# PowerManager.net
KiCad netlist of a schematic drawn in Altium Designer
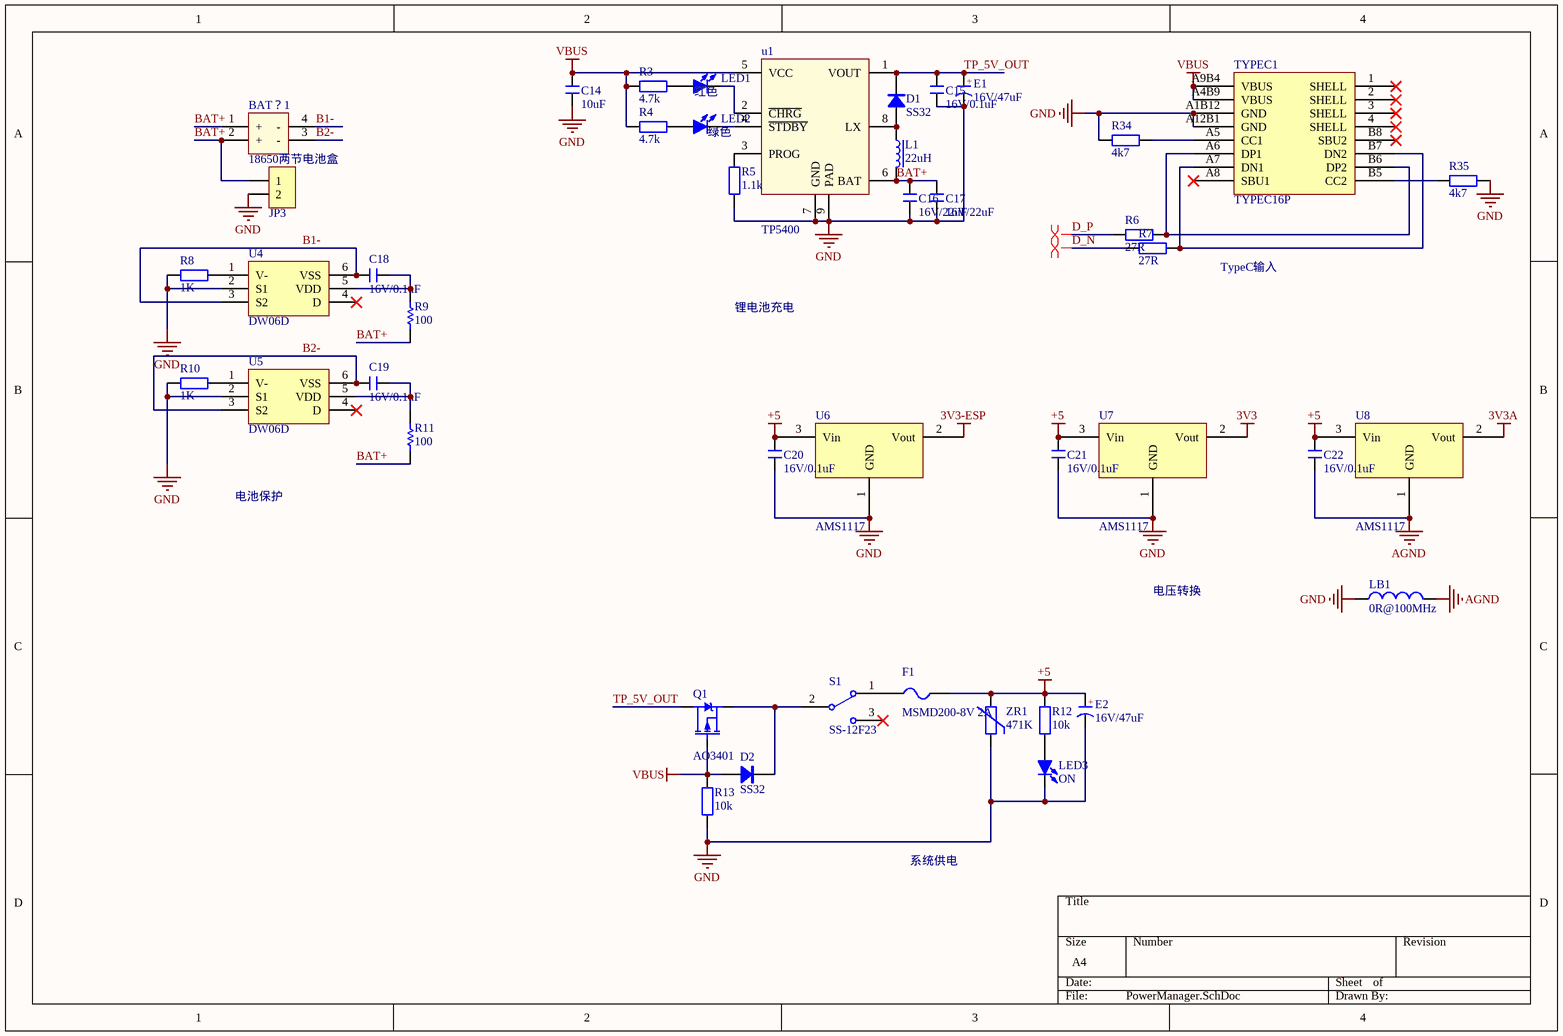
[diagram p0: PowerManager.SchDoc]

(export (version "E")
  (design (tool "Eeschema 10.0.6"))
  (components
    (comp (ref "BAT？1")
      (value "18650两节电池盒")
      (footprint "18650两节电池盒")
      (libsource (lib "Schlib1") (part "18650两节电池盒"))
    )
    (comp (ref "C14")
      (value "10uF")
      (footprint "C 0603_L")
      (description "无极性贴片电容")
      (fields (field (name "版权归属") "源创客"))
      (libsource (lib "3.1   - 电阻-电容-电感") (part "C"))
    )
    (comp (ref "C15")
      (value "16V/0.1uF")
      (footprint "C 1206_L")
      (description "无极性贴片电容")
      (fields (field (name "版权归属") "源创客"))
      (libsource (lib "3.1   - 电阻-电容-电感") (part "C"))
    )
    (comp (ref "C16")
      (value "16V/22uF")
      (footprint "C 1206_L")
      (description "无极性贴片电容")
      (fields (field (name "版权归属") "源创客"))
      (libsource (lib "3.1   - 电阻-电容-电感") (part "C"))
    )
    (comp (ref "C17")
      (value "16V/22uF")
      (footprint "C 1206_L")
      (description "无极性贴片电容")
      (fields (field (name "版权归属") "源创客"))
      (libsource (lib "3.1   - 电阻-电容-电感") (part "C"))
    )
    (comp (ref "C18")
      (value "16V/0.1uF")
      (footprint "C 1206_L")
      (description "无极性贴片电容")
      (fields (field (name "版权归属") "源创客"))
      (libsource (lib "3.1   - 电阻-电容-电感") (part "C"))
    )
    (comp (ref "C19")
      (value "16V/0.1uF")
      (footprint "C 1206_L")
      (description "无极性贴片电容")
      (fields (field (name "版权归属") "源创客"))
      (libsource (lib "3.1   - 电阻-电容-电感") (part "C"))
    )
    (comp (ref "C20")
      (value "16V/0.1uF")
      (footprint "C 1206_L")
      (description "无极性贴片电容")
      (fields (field (name "版权归属") "源创客"))
      (libsource (lib "3.1   - 电阻-电容-电感") (part "C"))
    )
    (comp (ref "C21")
      (value "16V/0.1uF")
      (footprint "C 1206_L")
      (description "无极性贴片电容")
      (fields (field (name "版权归属") "源创客"))
      (libsource (lib "3.1   - 电阻-电容-电感") (part "C"))
    )
    (comp (ref "C22")
      (value "16V/0.1uF")
      (footprint "C 1206_L")
      (description "无极性贴片电容")
      (fields (field (name "版权归属") "源创客"))
      (libsource (lib "3.1   - 电阻-电容-电感") (part "C"))
    )
    (comp (ref "D1")
      (value "SS32")
      (footprint "SMA")
      (description "肖特基二极管")
      (fields (field (name "版权归属") "源创客"))
      (libsource (lib "8.1   - 二极管-整流桥") (part "SS210"))
    )
    (comp (ref "D2")
      (value "SS32")
      (footprint "SMA")
      (description "肖特基二极管")
      (fields (field (name "版权归属") "源创客"))
      (libsource (lib "8.1   - 二极管-整流桥") (part "SS210"))
    )
    (comp (ref "E1")
      (value "16V/47uF")
      (footprint "CM C(5*5.4)")
      (description "贴片电解电容")
      (fields (field (name "版权归属") "源创客"))
      (libsource (lib "3.1   - 电阻-电容-电感") (part "C-CM"))
    )
    (comp (ref "E2")
      (value "16V/47uF")
      (footprint "CM C(5*5.4)")
      (description "贴片电解电容")
      (fields (field (name "版权归属") "源创客"))
      (libsource (lib "3.1   - 电阻-电容-电感") (part "C-CM"))
    )
    (comp (ref "F1")
      (value "MSMD200-8V 2A")
      (footprint "FU 1206")
      (description "贴片保险丝")
      (fields (field (name "版权归属") "源创客"))
      (libsource (lib "10.1 - 保险丝-晶振") (part "FU"))
    )
    (comp (ref "JP3")
      (value "HDR-1X2")
      (footprint "XH2.54-WS-2P")
      (description "2P接插件")
      (fields (field (name "版权归属") "源创客"))
      (libsource (lib "4.6   - 接插件-脚距2.54") (part "Header 2"))
    )
    (comp (ref "L1")
      (value "22uH")
      (footprint "NR4020")
      (description "NR磁胶电感")
      (fields (field (name "版权归属") "源创客"))
      (libsource (lib "3.1   - 电阻-电容-电感") (part "L-NR"))
    )
    (comp (ref "LB1")
      (value "0R@100MHz")
      (footprint "FB 1206_L")
      (description "磁珠")
      (fields (field (name "版权归属") "源创客"))
      (libsource (lib "3.1   - 电阻-电容-电感") (part "LB"))
    )
    (comp (ref "LED1")
      (value "红色")
      (footprint "LED 0603R")
      (description "贴片LED")
      (fields (field (name "版权归属") "源创客"))
      (libsource (lib "9.1   - LED") (part "LED-SMD"))
    )
    (comp (ref "LED2")
      (value "绿色")
      (footprint "LED 0603G")
      (description "贴片LED")
      (fields (field (name "版权归属") "源创客"))
      (libsource (lib "9.1   - LED") (part "LED-SMD"))
    )
    (comp (ref "LED3")
      (value "ON")
      (footprint "LED 0603R")
      (description "贴片LED")
      (fields (field (name "版权归属") "源创客"))
      (libsource (lib "9.1   - LED") (part "LED-SMD"))
    )
    (comp (ref "Q1")
      (value "AO3401")
      (footprint "SOT23")
      (description "P沟道场效应管")
      (libsource (lib "MOS管") (part "P-MOS"))
    )
    (comp (ref "R3")
      (value "4.7k")
      (footprint "R 0603_L")
      (description "贴片电阻")
      (fields (field (name "版权归属") "源创客"))
      (libsource (lib "3.1   - 电阻-电容-电感") (part "R"))
    )
    (comp (ref "R4")
      (value "4.7k")
      (footprint "R 0603_L")
      (description "贴片电阻")
      (fields (field (name "版权归属") "源创客"))
      (libsource (lib "3.1   - 电阻-电容-电感") (part "R"))
    )
    (comp (ref "R5")
      (value "1.1k")
      (footprint "R 0603_L")
      (description "贴片电阻")
      (fields (field (name "版权归属") "源创客"))
      (libsource (lib "3.1   - 电阻-电容-电感") (part "R"))
    )
    (comp (ref "R6")
      (value "27R")
      (footprint "R 0603_L")
      (description "贴片电阻")
      (fields (field (name "版权归属") "源创客"))
      (libsource (lib "3.1   - 电阻-电容-电感") (part "R"))
    )
    (comp (ref "R7")
      (value "27R")
      (footprint "R 0603_L")
      (description "贴片电阻")
      (fields (field (name "版权归属") "源创客"))
      (libsource (lib "3.1   - 电阻-电容-电感") (part "R"))
    )
    (comp (ref "R8")
      (value "1K")
      (footprint "R 0603_L")
      (description "贴片电阻")
      (fields (field (name "版权归属") "源创客"))
      (libsource (lib "3.1   - 电阻-电容-电感") (part "R"))
    )
    (comp (ref "R9") (value "100") (footprint "0603R") (libsource (lib "电阻") (part "RES")))
    (comp (ref "R10")
      (value "1K")
      (footprint "R 0603_L")
      (description "贴片电阻")
      (fields (field (name "版权归属") "源创客"))
      (libsource (lib "3.1   - 电阻-电容-电感") (part "R"))
    )
    (comp (ref "R11") (value "100") (footprint "0603R") (libsource (lib "电阻") (part "RES")))
    (comp (ref "R12")
      (value "10k")
      (footprint "R 0603_L")
      (description "贴片电阻")
      (fields (field (name "版权归属") "源创客"))
      (libsource (lib "3.1   - 电阻-电容-电感") (part "R"))
    )
    (comp (ref "R13")
      (value "10k")
      (footprint "R 0603_L")
      (description "贴片电阻")
      (fields (field (name "版权归属") "源创客"))
      (libsource (lib "3.1   - 电阻-电容-电感") (part "R"))
    )
    (comp (ref "R34")
      (value "4k7")
      (footprint "R 0603_L")
      (description "贴片电阻")
      (fields (field (name "版权归属") "源创客"))
      (libsource (lib "3.1   - 电阻-电容-电感") (part "R"))
    )
    (comp (ref "R35")
      (value "4k7")
      (footprint "R 0603_L")
      (description "贴片电阻")
      (fields (field (name "版权归属") "源创客"))
      (libsource (lib "3.1   - 电阻-电容-电感") (part "R"))
    )
    (comp (ref "S1")
      (value "SS-12F23")
      (footprint "SK-12D07VG3")
      (description "1路波动开关")
      (fields (field (name "版权归属") "源创客"))
      (libsource (lib "5.1   - 按键-开关") (part "SSW-1P"))
    )
    (comp (ref "TYPEC1")
      (value "TYPEC16P")
      (footprint "TYPEC-16P")
      (libsource (lib "Schlib1") (part "TYPEC16P"))
    )
    (comp (ref "u1") (value "TP5400") (footprint "ESOP8") (libsource (lib "Schlib1") (part "TP5400")))
    (comp (ref "U4") (value "DW06D") (footprint "SOT23-6") (libsource (lib "Schlib1") (part "DW06D")))
    (comp (ref "U5") (value "DW06D") (footprint "SOT23-6") (libsource (lib "Schlib1") (part "DW06D")))
    (comp (ref "U6")
      (value "AMS1117")
      (footprint "SOT89")
      (description "三端稳压芯片")
      (libsource (lib "电源芯片") (part "AMS1117"))
    )
    (comp (ref "U7")
      (value "AMS1117")
      (footprint "SOT89")
      (description "三端稳压芯片")
      (libsource (lib "电源芯片") (part "AMS1117"))
    )
    (comp (ref "U8")
      (value "AMS1117")
      (footprint "SOT89")
      (description "三端稳压芯片")
      (libsource (lib "电源芯片") (part "AMS1117"))
    )
    (comp (ref "ZR1")
      (value "471K")
      (footprint "R 0603_L")
      (description "压敏电阻")
      (fields (field (name "版权归属") "源创客"))
      (libsource (lib "3.1   - 电阻-电容-电感") (part "R_VDR"))
    )
  )
  (nets
    (net (code "1") (name "+5") (class "Default")
      (node (ref "C20") (pin "2") (pinfunction "2_2") (pintype "passive"))
      (node (ref "C21") (pin "2") (pinfunction "2_2") (pintype "passive"))
      (node (ref "C22") (pin "2") (pinfunction "2_2") (pintype "passive"))
      (node (ref "E2") (pin "1") (pinfunction "A_1") (pintype "passive"))
      (node (ref "F1") (pin "2") (pinfunction "2_2") (pintype "passive"))
      (node (ref "R12") (pin "2") (pinfunction "2_2") (pintype "passive"))
      (node (ref "U6") (pin "3") (pinfunction "Vin_3") (pintype "passive"))
      (node (ref "U7") (pin "3") (pinfunction "Vin_3") (pintype "passive"))
      (node (ref "U8") (pin "3") (pinfunction "Vin_3") (pintype "passive"))
      (node (ref "ZR1") (pin "2") (pinfunction "2_2") (pintype "passive"))
    )
    (net (code "2") (name "/B1-") (class "Default")
      (node (ref "BAT？1") (pin "4") (pinfunction "-_4") (pintype "passive"))
      (node (ref "C18") (pin "2") (pinfunction "2_2") (pintype "passive"))
      (node (ref "U4") (pin "3") (pinfunction "S2_3") (pintype "passive"))
      (node (ref "U4") (pin "6") (pinfunction "VSS_6") (pintype "passive"))
    )
    (net (code "3") (name "/B2-") (class "Default")
      (node (ref "BAT？1") (pin "3") (pinfunction "-_3") (pintype "passive"))
      (node (ref "C19") (pin "2") (pinfunction "2_2") (pintype "passive"))
      (node (ref "U5") (pin "3") (pinfunction "S2_3") (pintype "passive"))
      (node (ref "U5") (pin "6") (pinfunction "VSS_6") (pintype "passive"))
    )
    (net (code "4") (name "/BAT+") (class "Default")
      (node (ref "BAT？1") (pin "1") (pinfunction "+_1") (pintype "passive"))
      (node (ref "BAT？1") (pin "2") (pinfunction "+_2") (pintype "passive"))
      (node (ref "C16") (pin "2") (pinfunction "2_2") (pintype "passive"))
      (node (ref "C17") (pin "2") (pinfunction "2_2") (pintype "passive"))
      (node (ref "JP3") (pin "1") (pinfunction "1_1") (pintype "passive"))
      (node (ref "L1") (pin "2") (pinfunction "2_2") (pintype "passive"))
      (node (ref "R11") (pin "2") (pinfunction "2_2") (pintype "passive"))
      (node (ref "R9") (pin "2") (pinfunction "2_2") (pintype "passive"))
      (node (ref "u1") (pin "6") (pinfunction "BAT_6") (pintype "passive"))
    )
    (net (code "5") (name "/D_N") (class "Default")
      (node (ref "R7") (pin "1") (pinfunction "1_1") (pintype "passive"))
    )
    (net (code "6") (name "/D_P") (class "Default")
      (node (ref "R6") (pin "1") (pinfunction "1_1") (pintype "passive"))
    )
    (net (code "7") (name "/TP_5V_OUT") (class "Default")
      (node (ref "C15") (pin "2") (pinfunction "2_2") (pintype "passive"))
      (node (ref "D1") (pin "2") (pinfunction "K_2") (pintype "passive"))
      (node (ref "E1") (pin "1") (pinfunction "A_1") (pintype "passive"))
      (node (ref "Q1") (pin "D") (pinfunction "D_D") (pintype "passive"))
      (node (ref "u1") (pin "1") (pinfunction "VOUT_1") (pintype "passive"))
    )
    (net (code "8") (name "3V3") (class "Default")
      (node (ref "U7") (pin "2") (pinfunction "Vout_2") (pintype "passive"))
    )
    (net (code "9") (name "3V3-ESP") (class "Default")
      (node (ref "U6") (pin "2") (pinfunction "Vout_2") (pintype "passive"))
    )
    (net (code "10") (name "3V3A") (class "Default")
      (node (ref "U8") (pin "2") (pinfunction "Vout_2") (pintype "passive"))
    )
    (net (code "11") (name "AGND") (class "Default")
      (node (ref "C22") (pin "1") (pinfunction "1_1") (pintype "passive"))
      (node (ref "LB1") (pin "2") (pinfunction "2_2") (pintype "passive"))
      (node (ref "U8") (pin "1") (pinfunction "GND_1") (pintype "passive"))
    )
    (net (code "12") (name "GND") (class "Default")
      (node (ref "C14") (pin "1") (pinfunction "1_1") (pintype "passive"))
      (node (ref "C15") (pin "1") (pinfunction "1_1") (pintype "passive"))
      (node (ref "C16") (pin "1") (pinfunction "1_1") (pintype "passive"))
      (node (ref "C17") (pin "1") (pinfunction "1_1") (pintype "passive"))
      (node (ref "C20") (pin "1") (pinfunction "1_1") (pintype "passive"))
      (node (ref "C21") (pin "1") (pinfunction "1_1") (pintype "passive"))
      (node (ref "E1") (pin "2") (pinfunction "K_2") (pintype "passive"))
      (node (ref "E2") (pin "2") (pinfunction "K_2") (pintype "passive"))
      (node (ref "JP3") (pin "2") (pinfunction "2_2") (pintype "passive"))
      (node (ref "LB1") (pin "1") (pinfunction "1_1") (pintype "passive"))
      (node (ref "LED3") (pin "2") (pinfunction "K_2") (pintype "passive"))
      (node (ref "R10") (pin "1") (pinfunction "1_1") (pintype "passive"))
      (node (ref "R13") (pin "1") (pinfunction "1_1") (pintype "passive"))
      (node (ref "R34") (pin "1") (pinfunction "1_1") (pintype "passive"))
      (node (ref "R35") (pin "1") (pinfunction "1_1") (pintype "passive"))
      (node (ref "R5") (pin "1") (pinfunction "1_1") (pintype "passive"))
      (node (ref "R8") (pin "1") (pinfunction "1_1") (pintype "passive"))
      (node (ref "TYPEC1") (pin "A12B1") (pinfunction "GND_A12B1") (pintype "passive"))
      (node (ref "TYPEC1") (pin "A1B12") (pinfunction "GND_A1B12") (pintype "passive"))
      (node (ref "U4") (pin "2") (pinfunction "S1_2") (pintype "passive"))
      (node (ref "U5") (pin "2") (pinfunction "S1_2") (pintype "passive"))
      (node (ref "U6") (pin "1") (pinfunction "GND_1") (pintype "passive"))
      (node (ref "U7") (pin "1") (pinfunction "GND_1") (pintype "passive"))
      (node (ref "ZR1") (pin "1") (pinfunction "1_1") (pintype "passive"))
      (node (ref "u1") (pin "7") (pinfunction "GND_7") (pintype "passive"))
      (node (ref "u1") (pin "9") (pinfunction "PAD_9") (pintype "passive"))
    )
    (net (code "13") (name "Net-(D1-A)") (class "Default")
      (node (ref "D1") (pin "1") (pinfunction "A_1") (pintype "passive"))
      (node (ref "L1") (pin "1") (pinfunction "1_1") (pintype "passive"))
      (node (ref "u1") (pin "8") (pinfunction "LX_8") (pintype "passive"))
    )
    (net (code "14") (name "Net-(D2-K)") (class "Default")
      (node (ref "D2") (pin "2") (pinfunction "K_2") (pintype "passive"))
      (node (ref "Q1") (pin "S") (pinfunction "S_S") (pintype "passive"))
      (node (ref "S1") (pin "2") (pinfunction "2_2") (pintype "passive"))
    )
    (net (code "15") (name "Net-(F1-Pad1)") (class "Default")
      (node (ref "F1") (pin "1") (pinfunction "1_1") (pintype "passive"))
      (node (ref "S1") (pin "1") (pinfunction "1_1") (pintype "passive"))
    )
    (net (code "16") (name "Net-(LED1-A)") (class "Default")
      (node (ref "LED1") (pin "1") (pinfunction "A_1") (pintype "passive"))
      (node (ref "R3") (pin "1") (pinfunction "1_1") (pintype "passive"))
    )
    (net (code "17") (name "Net-(LED1-K)") (class "Default")
      (node (ref "LED1") (pin "2") (pinfunction "K_2") (pintype "passive"))
      (node (ref "u1") (pin "2") (pinfunction "~{CHRG}_2") (pintype "passive"))
    )
    (net (code "18") (name "Net-(LED2-A)") (class "Default")
      (node (ref "LED2") (pin "1") (pinfunction "A_1") (pintype "passive"))
      (node (ref "R4") (pin "1") (pinfunction "1_1") (pintype "passive"))
    )
    (net (code "19") (name "Net-(LED2-K)") (class "Default")
      (node (ref "LED2") (pin "2") (pinfunction "K_2") (pintype "passive"))
      (node (ref "u1") (pin "4") (pinfunction "~{STDBY}_4") (pintype "passive"))
    )
    (net (code "20") (name "Net-(LED3-A)") (class "Default")
      (node (ref "LED3") (pin "1") (pinfunction "A_1") (pintype "passive"))
      (node (ref "R12") (pin "1") (pinfunction "1_1") (pintype "passive"))
    )
    (net (code "21") (name "Net-(TYPEC1-CC1)") (class "Default")
      (node (ref "R34") (pin "2") (pinfunction "2_2") (pintype "passive"))
      (node (ref "TYPEC1") (pin "A5") (pinfunction "CC1_A5") (pintype "passive"))
    )
    (net (code "22") (name "Net-(TYPEC1-CC2)") (class "Default")
      (node (ref "R35") (pin "2") (pinfunction "2_2") (pintype "passive"))
      (node (ref "TYPEC1") (pin "B5") (pinfunction "CC2_B5") (pintype "passive"))
    )
    (net (code "23") (name "Net-(TYPEC1-DN1)") (class "Default")
      (node (ref "R7") (pin "2") (pinfunction "2_2") (pintype "passive"))
      (node (ref "TYPEC1") (pin "A7") (pinfunction "DN1_A7") (pintype "passive"))
      (node (ref "TYPEC1") (pin "B7") (pinfunction "DN2_B7") (pintype "passive"))
    )
    (net (code "24") (name "Net-(TYPEC1-DP1)") (class "Default")
      (node (ref "R6") (pin "2") (pinfunction "2_2") (pintype "passive"))
      (node (ref "TYPEC1") (pin "A6") (pinfunction "DP1_A6") (pintype "passive"))
      (node (ref "TYPEC1") (pin "B6") (pinfunction "DP2_B6") (pintype "passive"))
    )
    (net (code "25") (name "Net-(U4-V-)") (class "Default")
      (node (ref "R8") (pin "2") (pinfunction "2_2") (pintype "passive"))
      (node (ref "U4") (pin "1") (pinfunction "V-_1") (pintype "passive"))
    )
    (net (code "26") (name "Net-(U4-VDD)") (class "Default")
      (node (ref "C18") (pin "1") (pinfunction "1_1") (pintype "passive"))
      (node (ref "R9") (pin "1") (pinfunction "1_1") (pintype "passive"))
      (node (ref "U4") (pin "5") (pinfunction "VDD_5") (pintype "passive"))
    )
    (net (code "27") (name "Net-(U5-V-)") (class "Default")
      (node (ref "R10") (pin "2") (pinfunction "2_2") (pintype "passive"))
      (node (ref "U5") (pin "1") (pinfunction "V-_1") (pintype "passive"))
    )
    (net (code "28") (name "Net-(U5-VDD)") (class "Default")
      (node (ref "C19") (pin "1") (pinfunction "1_1") (pintype "passive"))
      (node (ref "R11") (pin "1") (pinfunction "1_1") (pintype "passive"))
      (node (ref "U5") (pin "5") (pinfunction "VDD_5") (pintype "passive"))
    )
    (net (code "29") (name "Net-(u1-PROG)") (class "Default")
      (node (ref "R5") (pin "2") (pinfunction "2_2") (pintype "passive"))
      (node (ref "u1") (pin "3") (pinfunction "PROG_3") (pintype "passive"))
    )
    (net (code "30") (name "VBUS") (class "Default")
      (node (ref "C14") (pin "2") (pinfunction "2_2") (pintype "passive"))
      (node (ref "D2") (pin "1") (pinfunction "A_1") (pintype "passive"))
      (node (ref "Q1") (pin "G") (pinfunction "G_G") (pintype "passive"))
      (node (ref "R13") (pin "2") (pinfunction "2_2") (pintype "passive"))
      (node (ref "R3") (pin "2") (pinfunction "2_2") (pintype "passive"))
      (node (ref "R4") (pin "2") (pinfunction "2_2") (pintype "passive"))
      (node (ref "TYPEC1") (pin "A4B9") (pinfunction "VBUS_A4B9") (pintype "passive"))
      (node (ref "TYPEC1") (pin "A9B4") (pinfunction "VBUS_A9B4") (pintype "passive"))
      (node (ref "u1") (pin "5") (pinfunction "VCC_5") (pintype "passive"))
    )
    (net (code "31") (name "unconnected-(S1-Pad3)") (class "Default")
      (node (ref "S1") (pin "3") (pinfunction "3_3") (pintype "passive+no_connect"))
    )
    (net (code "32") (name "unconnected-(TYPEC1-SBU1-PadA8)") (class "Default")
      (node (ref "TYPEC1") (pin "A8") (pinfunction "SBU1_A8") (pintype "passive+no_connect"))
    )
    (net (code "33") (name "unconnected-(TYPEC1-SBU2-PadB8)") (class "Default")
      (node (ref "TYPEC1") (pin "B8") (pinfunction "SBU2_B8") (pintype "passive+no_connect"))
    )
    (net (code "34") (name "unconnected-(TYPEC1-SHELL-Pad1)") (class "Default")
      (node (ref "TYPEC1") (pin "1") (pinfunction "SHELL_1") (pintype "passive+no_connect"))
    )
    (net (code "35") (name "unconnected-(TYPEC1-SHELL-Pad2)") (class "Default")
      (node (ref "TYPEC1") (pin "2") (pinfunction "SHELL_2") (pintype "passive+no_connect"))
    )
    (net (code "36") (name "unconnected-(TYPEC1-SHELL-Pad3)") (class "Default")
      (node (ref "TYPEC1") (pin "3") (pinfunction "SHELL_3") (pintype "passive+no_connect"))
    )
    (net (code "37") (name "unconnected-(TYPEC1-SHELL-Pad4)") (class "Default")
      (node (ref "TYPEC1") (pin "4") (pinfunction "SHELL_4") (pintype "passive+no_connect"))
    )
    (net (code "38") (name "unconnected-(U4-D-Pad4)") (class "Default")
      (node (ref "U4") (pin "4") (pinfunction "D_4") (pintype "passive+no_connect"))
    )
    (net (code "39") (name "unconnected-(U5-D-Pad4)") (class "Default")
      (node (ref "U5") (pin "4") (pinfunction "D_4") (pintype "passive+no_connect"))
    )
  )
)
